# TSAL_Revisado.net
KiCad netlist of a schematic drawn in EAGLE
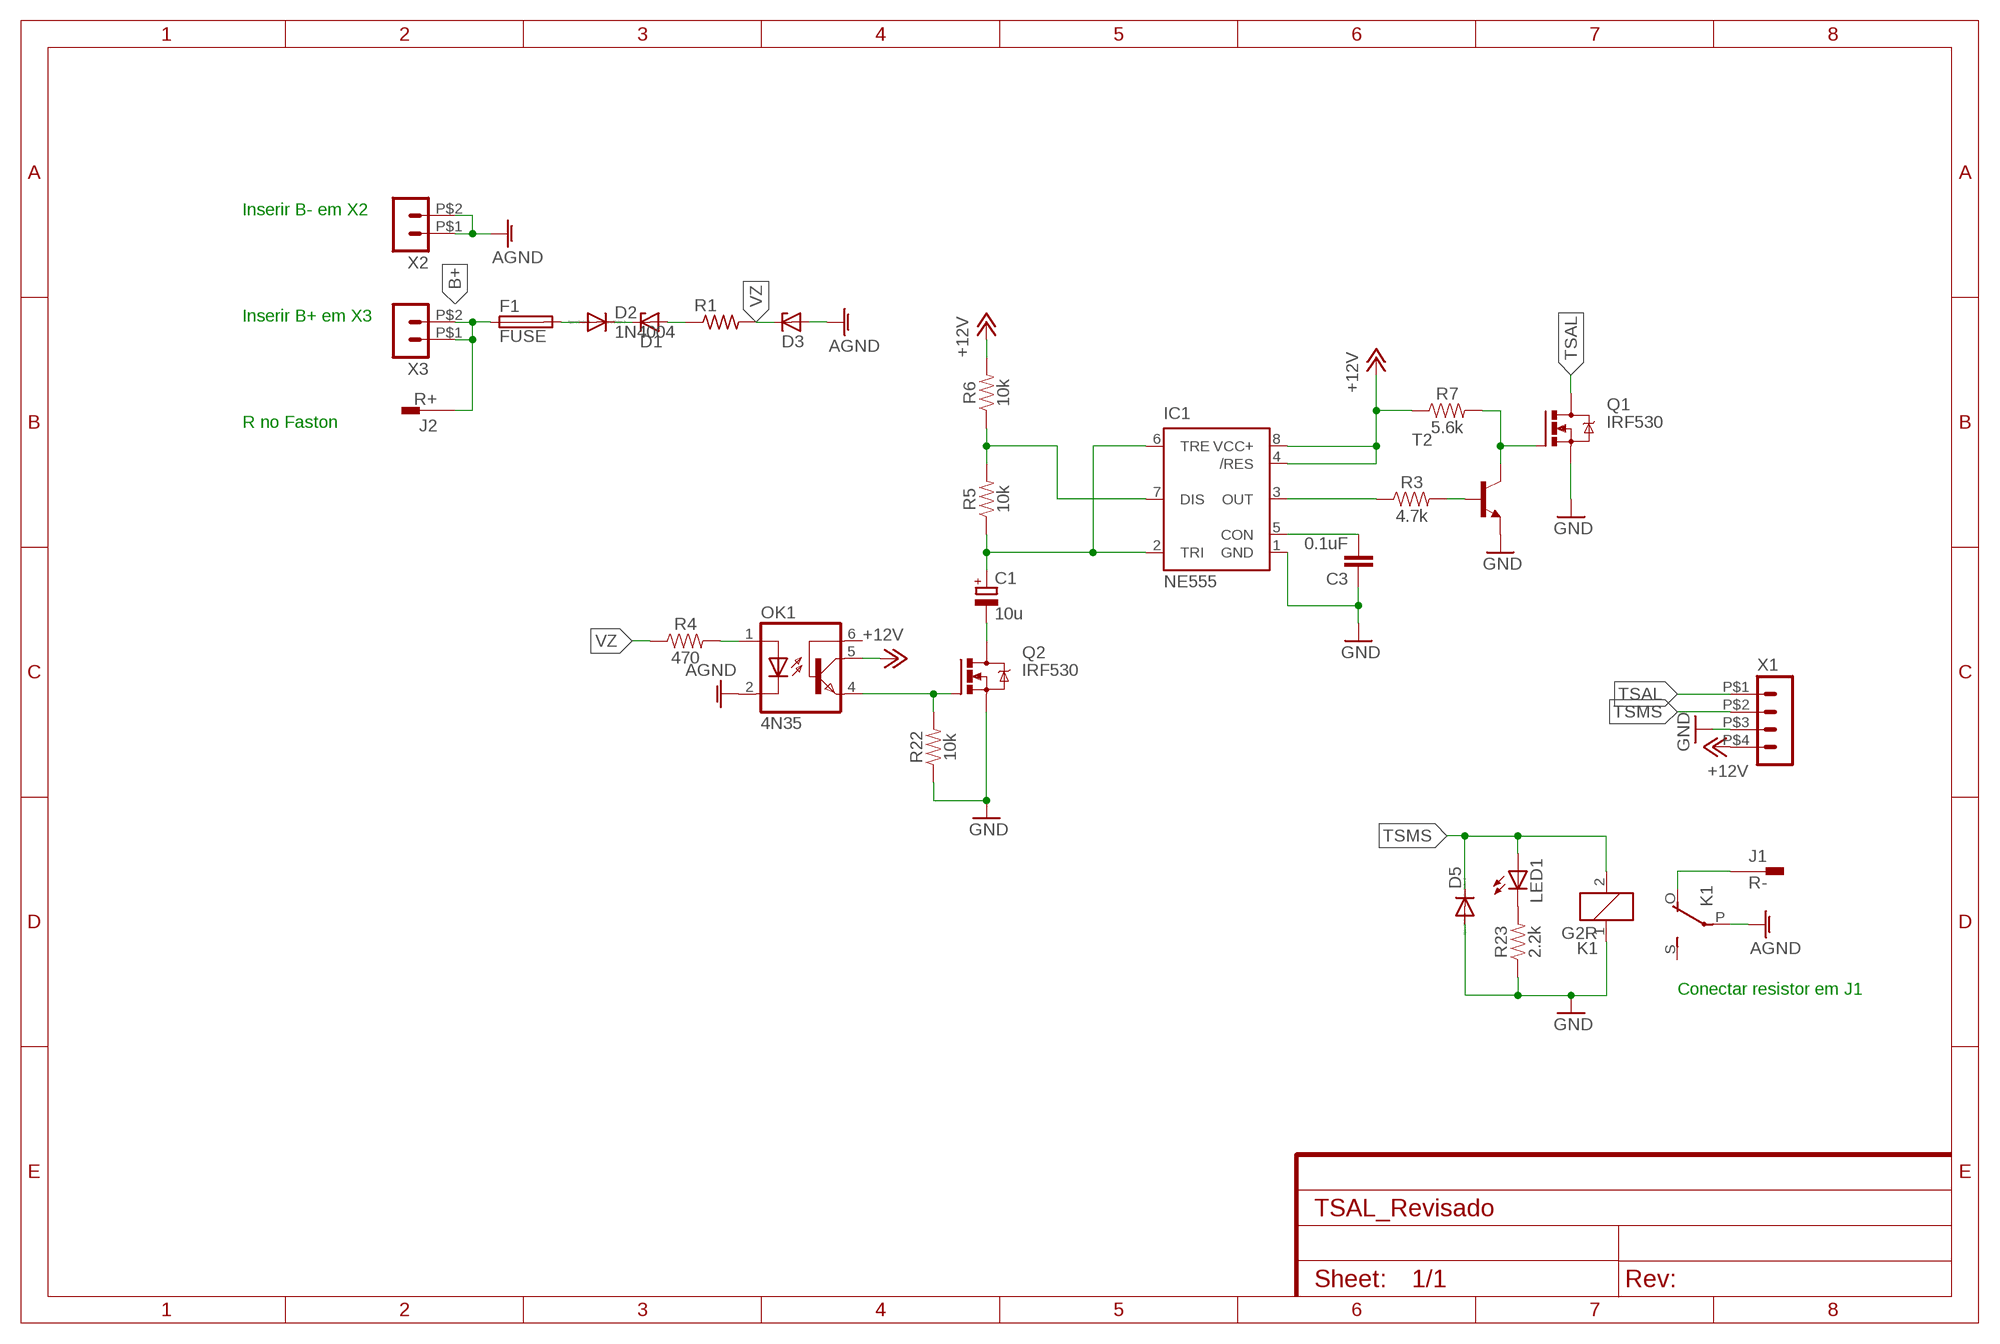
[diagram p0: schematic, sheet 1]

(export (version "E")
  (design (tool "Eeschema 10.0.6"))
  (components
    (comp (ref "C1")
      (value "10u")
      (footprint "eagle-import:E2-5")
      (libsource (lib "eagle-import") (part "CPOL-EUE2-5"))
    )
    (comp (ref "C3")
      (value "0.1uF")
      (footprint "eagle-import:CAP-PTH-SMALL-KIT")
      (libsource (lib "eagle-import") (part "0.1UF-KIT-EZ-50V-20%"))
    )
    (comp (ref "D1")
      (value "ZENER-DIODEDO41Z10")
      (footprint "eagle-import:DO41Z10")
      (libsource (lib "eagle-import") (part "ZENER-DIODEDO41Z10"))
    )
    (comp (ref "D2")
      (value "1N4004")
      (footprint "eagle-import:DO41-10")
      (libsource (lib "eagle-import") (part "1N4004"))
    )
    (comp (ref "D3")
      (value "ZENER-DIODEDO41Z10")
      (footprint "eagle-import:DO41Z10")
      (libsource (lib "eagle-import") (part "ZENER-DIODEDO41Z10"))
    )
    (comp (ref "D5")
      (value "1N4148DO35-10")
      (footprint "eagle-import:DO35-10")
      (libsource (lib "eagle-import") (part "1N4148DO35-10"))
    )
    (comp (ref "F1")
      (value "FUSE")
      (footprint "eagle-import:FUSE_HOLDER_5X20MM")
      (libsource (lib "eagle-import") (part "FUSEBLANK_5X20MM"))
    )
    (comp (ref "IC1")
      (value "NE555")
      (footprint "eagle-import:DIL-08")
      (fields (field (name "MF") "Arrow Electronics") (field (name "MPN") "NE555N"))
      (libsource (lib "eagle-import") (part "NE555"))
    )
    (comp (ref "J1")
      (value "R-")
      (footprint "eagle-import:F061.080")
      (libsource (lib "eagle-import") (part "PIN2F061.080"))
    )
    (comp (ref "J2")
      (value "R+")
      (footprint "eagle-import:F061.080")
      (libsource (lib "eagle-import") (part "PIN2F061.080"))
    )
    (comp (ref "K1")
      (value "G2R")
      (footprint "eagle-import:G2R")
      (libsource (lib "eagle-import") (part "G2R"))
    )
    (comp (ref "LED1")
      (value "LED3MM")
      (footprint "eagle-import:LED3MM")
      (libsource (lib "eagle-import") (part "LED3MM"))
    )
    (comp (ref "OK1")
      (value "4N35")
      (footprint "eagle-import:DIL06")
      (fields (field (name "MF") "FAIRCHILD SEMICONDUCTOR"))
      (libsource (lib "eagle-import") (part "4N35"))
    )
    (comp (ref "Q1")
      (value "IRF530")
      (footprint "eagle-import:TO220BV")
      (libsource (lib "eagle-import") (part "IRF530"))
    )
    (comp (ref "Q2")
      (value "IRF530")
      (footprint "eagle-import:TO220BV")
      (libsource (lib "eagle-import") (part "IRF530"))
    )
    (comp (ref "R1")
      (value "R-US_0207/15")
      (footprint "eagle-import:0207_15")
      (libsource (lib "eagle-import") (part "R-US_0207/15"))
    )
    (comp (ref "R3")
      (value "4.7k")
      (footprint "eagle-import:AXIAL-0.3")
      (libsource (lib "eagle-import") (part "SparkFun-Resistors_532_RESISTORAXIAL-0.3"))
    )
    (comp (ref "R4")
      (value "470")
      (footprint "eagle-import:AXIAL-0.3")
      (libsource (lib "eagle-import") (part "RESISTORAXIAL-0.3"))
    )
    (comp (ref "R5")
      (value "10k")
      (footprint "eagle-import:AXIAL-0.3")
      (libsource (lib "eagle-import") (part "RESISTORAXIAL-0.3"))
    )
    (comp (ref "R6")
      (value "10k")
      (footprint "eagle-import:AXIAL-0.3")
      (libsource (lib "eagle-import") (part "RESISTORAXIAL-0.3"))
    )
    (comp (ref "R7")
      (value "5.6k")
      (footprint "eagle-import:AXIAL-0.3")
      (libsource (lib "eagle-import") (part "SparkFun-Resistors_532_RESISTORAXIAL-0.3"))
    )
    (comp (ref "R22")
      (value "10k")
      (footprint "eagle-import:AXIAL-0.3")
      (libsource (lib "eagle-import") (part "RESISTORAXIAL-0.3"))
    )
    (comp (ref "R23")
      (value "2.2k")
      (footprint "eagle-import:AXIAL-0.3")
      (libsource (lib "eagle-import") (part "SparkFun-Resistors_532_RESISTORAXIAL-0.3"))
    )
    (comp (ref "T2")
      (value "BC337-NPN-TO92-CBE")
      (footprint "eagle-import:TO92-CBE")
      (libsource (lib "eagle-import") (part "-NPN-TO92-CBEBC337"))
    )
    (comp (ref "X1")
      (value "HEADER_POS4_43045-0401")
      (footprint "eagle-import:43045-0400")
      (libsource (lib "eagle-import") (part "HEADER_POS4_?43045-0401"))
    )
    (comp (ref "X2")
      (value "HEADER_POS2_43650-0200")
      (footprint "eagle-import:43650-0200")
      (libsource (lib "eagle-import") (part "HEADER_POS2_?43650-0200"))
    )
    (comp (ref "X3")
      (value "HEADER_POS2_43650-0200")
      (footprint "eagle-import:43650-0200")
      (libsource (lib "eagle-import") (part "HEADER_POS2_?43650-0200"))
    )
  )
  (nets
    (net (code "1") (name "+12V") (class "Default")
      (node (ref "IC1") (pin "4") (pinfunction "/RES_4") (pintype "input"))
      (node (ref "IC1") (pin "8") (pinfunction "VCC+_8") (pintype "power_in"))
      (node (ref "OK1") (pin "5") (pinfunction "COL_5") (pintype "passive"))
      (node (ref "R6") (pin "P$2") (pinfunction "2_P$2") (pintype "passive"))
      (node (ref "R7") (pin "P$1") (pinfunction "1_P$1") (pintype "passive"))
      (node (ref "X1") (pin "P$4") (pinfunction "4_P$4") (pintype "passive"))
    )
    (net (code "2") (name "AGND") (class "Default")
      (node (ref "D3") (pin "A") (pinfunction "A_A") (pintype "passive"))
      (node (ref "K1") (pin "P") (pinfunction "P_P") (pintype "passive"))
      (node (ref "OK1") (pin "2") (pinfunction "C_2") (pintype "passive"))
      (node (ref "X2") (pin "P$1") (pinfunction "1_P$1") (pintype "passive"))
      (node (ref "X2") (pin "P$2") (pinfunction "2_P$2") (pintype "passive"))
    )
    (net (code "3") (name "B+") (class "Default")
      (node (ref "F1") (pin "1") (pinfunction "1_1") (pintype "passive"))
      (node (ref "J2") (pin "1A") (pinfunction "1_1A") (pintype "passive"))
      (node (ref "J2") (pin "1B") (pinfunction "1_1B") (pintype "passive"))
      (node (ref "X3") (pin "P$1") (pinfunction "1_P$1") (pintype "passive"))
      (node (ref "X3") (pin "P$2") (pinfunction "2_P$2") (pintype "passive"))
    )
    (net (code "4") (name "GND") (class "Default")
      (node (ref "C3") (pin "1") (pinfunction "1_1") (pintype "passive"))
      (node (ref "D5") (pin "A") (pinfunction "A_A") (pintype "passive"))
      (node (ref "IC1") (pin "1") (pinfunction "GND_1") (pintype "power_in"))
      (node (ref "K1") (pin "1") (pinfunction "1_1") (pintype "passive"))
      (node (ref "Q1") (pin "S") (pinfunction "S_S") (pintype "passive"))
      (node (ref "Q2") (pin "S") (pinfunction "S_S") (pintype "passive"))
      (node (ref "R22") (pin "P$1") (pinfunction "1_P$1") (pintype "passive"))
      (node (ref "R23") (pin "P$1") (pinfunction "1_P$1") (pintype "passive"))
      (node (ref "T2") (pin "E") (pinfunction "E_E") (pintype "passive"))
      (node (ref "X1") (pin "P$3") (pinfunction "3_P$3") (pintype "passive"))
    )
    (net (code "5") (name "Net-(C1-Pad-)") (class "Default")
      (node (ref "C1") (pin "-") (pinfunction "-_-") (pintype "passive"))
      (node (ref "Q2") (pin "D") (pinfunction "D_D") (pintype "passive"))
    )
    (net (code "6") (name "Net-(D1-PadA)") (class "Default")
      (node (ref "D1") (pin "A") (pinfunction "A_A") (pintype "passive"))
      (node (ref "R1") (pin "1") (pinfunction "1_1") (pintype "passive"))
    )
    (net (code "7") (name "Net-(D1-PadC)") (class "Default")
      (node (ref "D1") (pin "C") (pinfunction "C_C") (pintype "passive"))
      (node (ref "D2") (pin "C") (pinfunction "C_C") (pintype "passive"))
    )
    (net (code "8") (name "Net-(D2-PadA)") (class "Default")
      (node (ref "D2") (pin "A") (pinfunction "A_A") (pintype "passive"))
      (node (ref "F1") (pin "2") (pinfunction "2_2") (pintype "passive"))
    )
    (net (code "9") (name "Net-(IC1-CON)") (class "Default")
      (node (ref "C3") (pin "2") (pinfunction "2_2") (pintype "passive"))
      (node (ref "IC1") (pin "5") (pinfunction "CON_5") (pintype "input"))
    )
    (net (code "10") (name "Net-(IC1-DIS)") (class "Default")
      (node (ref "IC1") (pin "7") (pinfunction "DIS_7") (pintype "input"))
      (node (ref "R5") (pin "P$2") (pinfunction "2_P$2") (pintype "passive"))
      (node (ref "R6") (pin "P$1") (pinfunction "1_P$1") (pintype "passive"))
    )
    (net (code "11") (name "Net-(IC1-OUT)") (class "Default")
      (node (ref "IC1") (pin "3") (pinfunction "OUT_3") (pintype "output"))
      (node (ref "R3") (pin "P$1") (pinfunction "1_P$1") (pintype "passive"))
    )
    (net (code "12") (name "Net-(IC1-TRE)") (class "Default")
      (node (ref "C1") (pin "+") (pinfunction "+_+") (pintype "passive"))
      (node (ref "IC1") (pin "2") (pinfunction "TRI_2") (pintype "input"))
      (node (ref "IC1") (pin "6") (pinfunction "TRE_6") (pintype "input"))
      (node (ref "R5") (pin "P$1") (pinfunction "1_P$1") (pintype "passive"))
    )
    (net (code "13") (name "Net-(J1-1-Pad1A)") (class "Default")
      (node (ref "J1") (pin "1A") (pinfunction "1_1A") (pintype "passive"))
      (node (ref "J1") (pin "1B") (pinfunction "1_1B") (pintype "passive"))
      (node (ref "K1") (pin "O") (pinfunction "O_O") (pintype "passive"))
    )
    (net (code "14") (name "Net-(LED1-C)") (class "Default")
      (node (ref "LED1") (pin "K") (pinfunction "C_K") (pintype "passive"))
      (node (ref "R23") (pin "P$2") (pinfunction "2_P$2") (pintype "passive"))
    )
    (net (code "15") (name "Net-(OK1-A)") (class "Default")
      (node (ref "OK1") (pin "1") (pinfunction "A_1") (pintype "passive"))
      (node (ref "R4") (pin "P$2") (pinfunction "2_P$2") (pintype "passive"))
    )
    (net (code "16") (name "Net-(OK1-EMI)") (class "Default")
      (node (ref "OK1") (pin "4") (pinfunction "EMI_4") (pintype "passive"))
      (node (ref "Q2") (pin "G") (pinfunction "G_G") (pintype "passive"))
      (node (ref "R22") (pin "P$2") (pinfunction "2_P$2") (pintype "passive"))
    )
    (net (code "17") (name "Net-(R3-2)") (class "Default")
      (node (ref "R3") (pin "P$2") (pinfunction "2_P$2") (pintype "passive"))
      (node (ref "T2") (pin "B") (pinfunction "B_B") (pintype "passive"))
    )
    (net (code "18") (name "Net-(R7-2)") (class "Default")
      (node (ref "Q1") (pin "G") (pinfunction "G_G") (pintype "passive"))
      (node (ref "R7") (pin "P$2") (pinfunction "2_P$2") (pintype "passive"))
      (node (ref "T2") (pin "C") (pinfunction "C_C") (pintype "passive"))
    )
    (net (code "19") (name "TSAL") (class "Default")
      (node (ref "Q1") (pin "D") (pinfunction "D_D") (pintype "passive"))
      (node (ref "X1") (pin "P$1") (pinfunction "1_P$1") (pintype "passive"))
    )
    (net (code "20") (name "TSMS") (class "Default")
      (node (ref "D5") (pin "C") (pinfunction "C_C") (pintype "passive"))
      (node (ref "K1") (pin "2") (pinfunction "2_2") (pintype "passive"))
      (node (ref "LED1") (pin "A") (pinfunction "A_A") (pintype "passive"))
      (node (ref "X1") (pin "P$2") (pinfunction "2_P$2") (pintype "passive"))
    )
    (net (code "21") (name "VZ") (class "Default")
      (node (ref "D3") (pin "C") (pinfunction "C_C") (pintype "passive"))
      (node (ref "R1") (pin "2") (pinfunction "2_2") (pintype "passive"))
      (node (ref "R4") (pin "P$1") (pinfunction "1_P$1") (pintype "passive"))
    )
    (net (code "22") (name "unconnected-(K1-PadS)") (class "Default")
      (node (ref "K1") (pin "S") (pinfunction "S_S") (pintype "passive"))
    )
    (net (code "23") (name "unconnected-(OK1-BAS-Pad6)") (class "Default")
      (node (ref "OK1") (pin "6") (pinfunction "BAS_6") (pintype "passive"))
    )
  )
)
